# 468323_001_Interface.net
KiCad netlist of a schematic drawn in Altium Designer
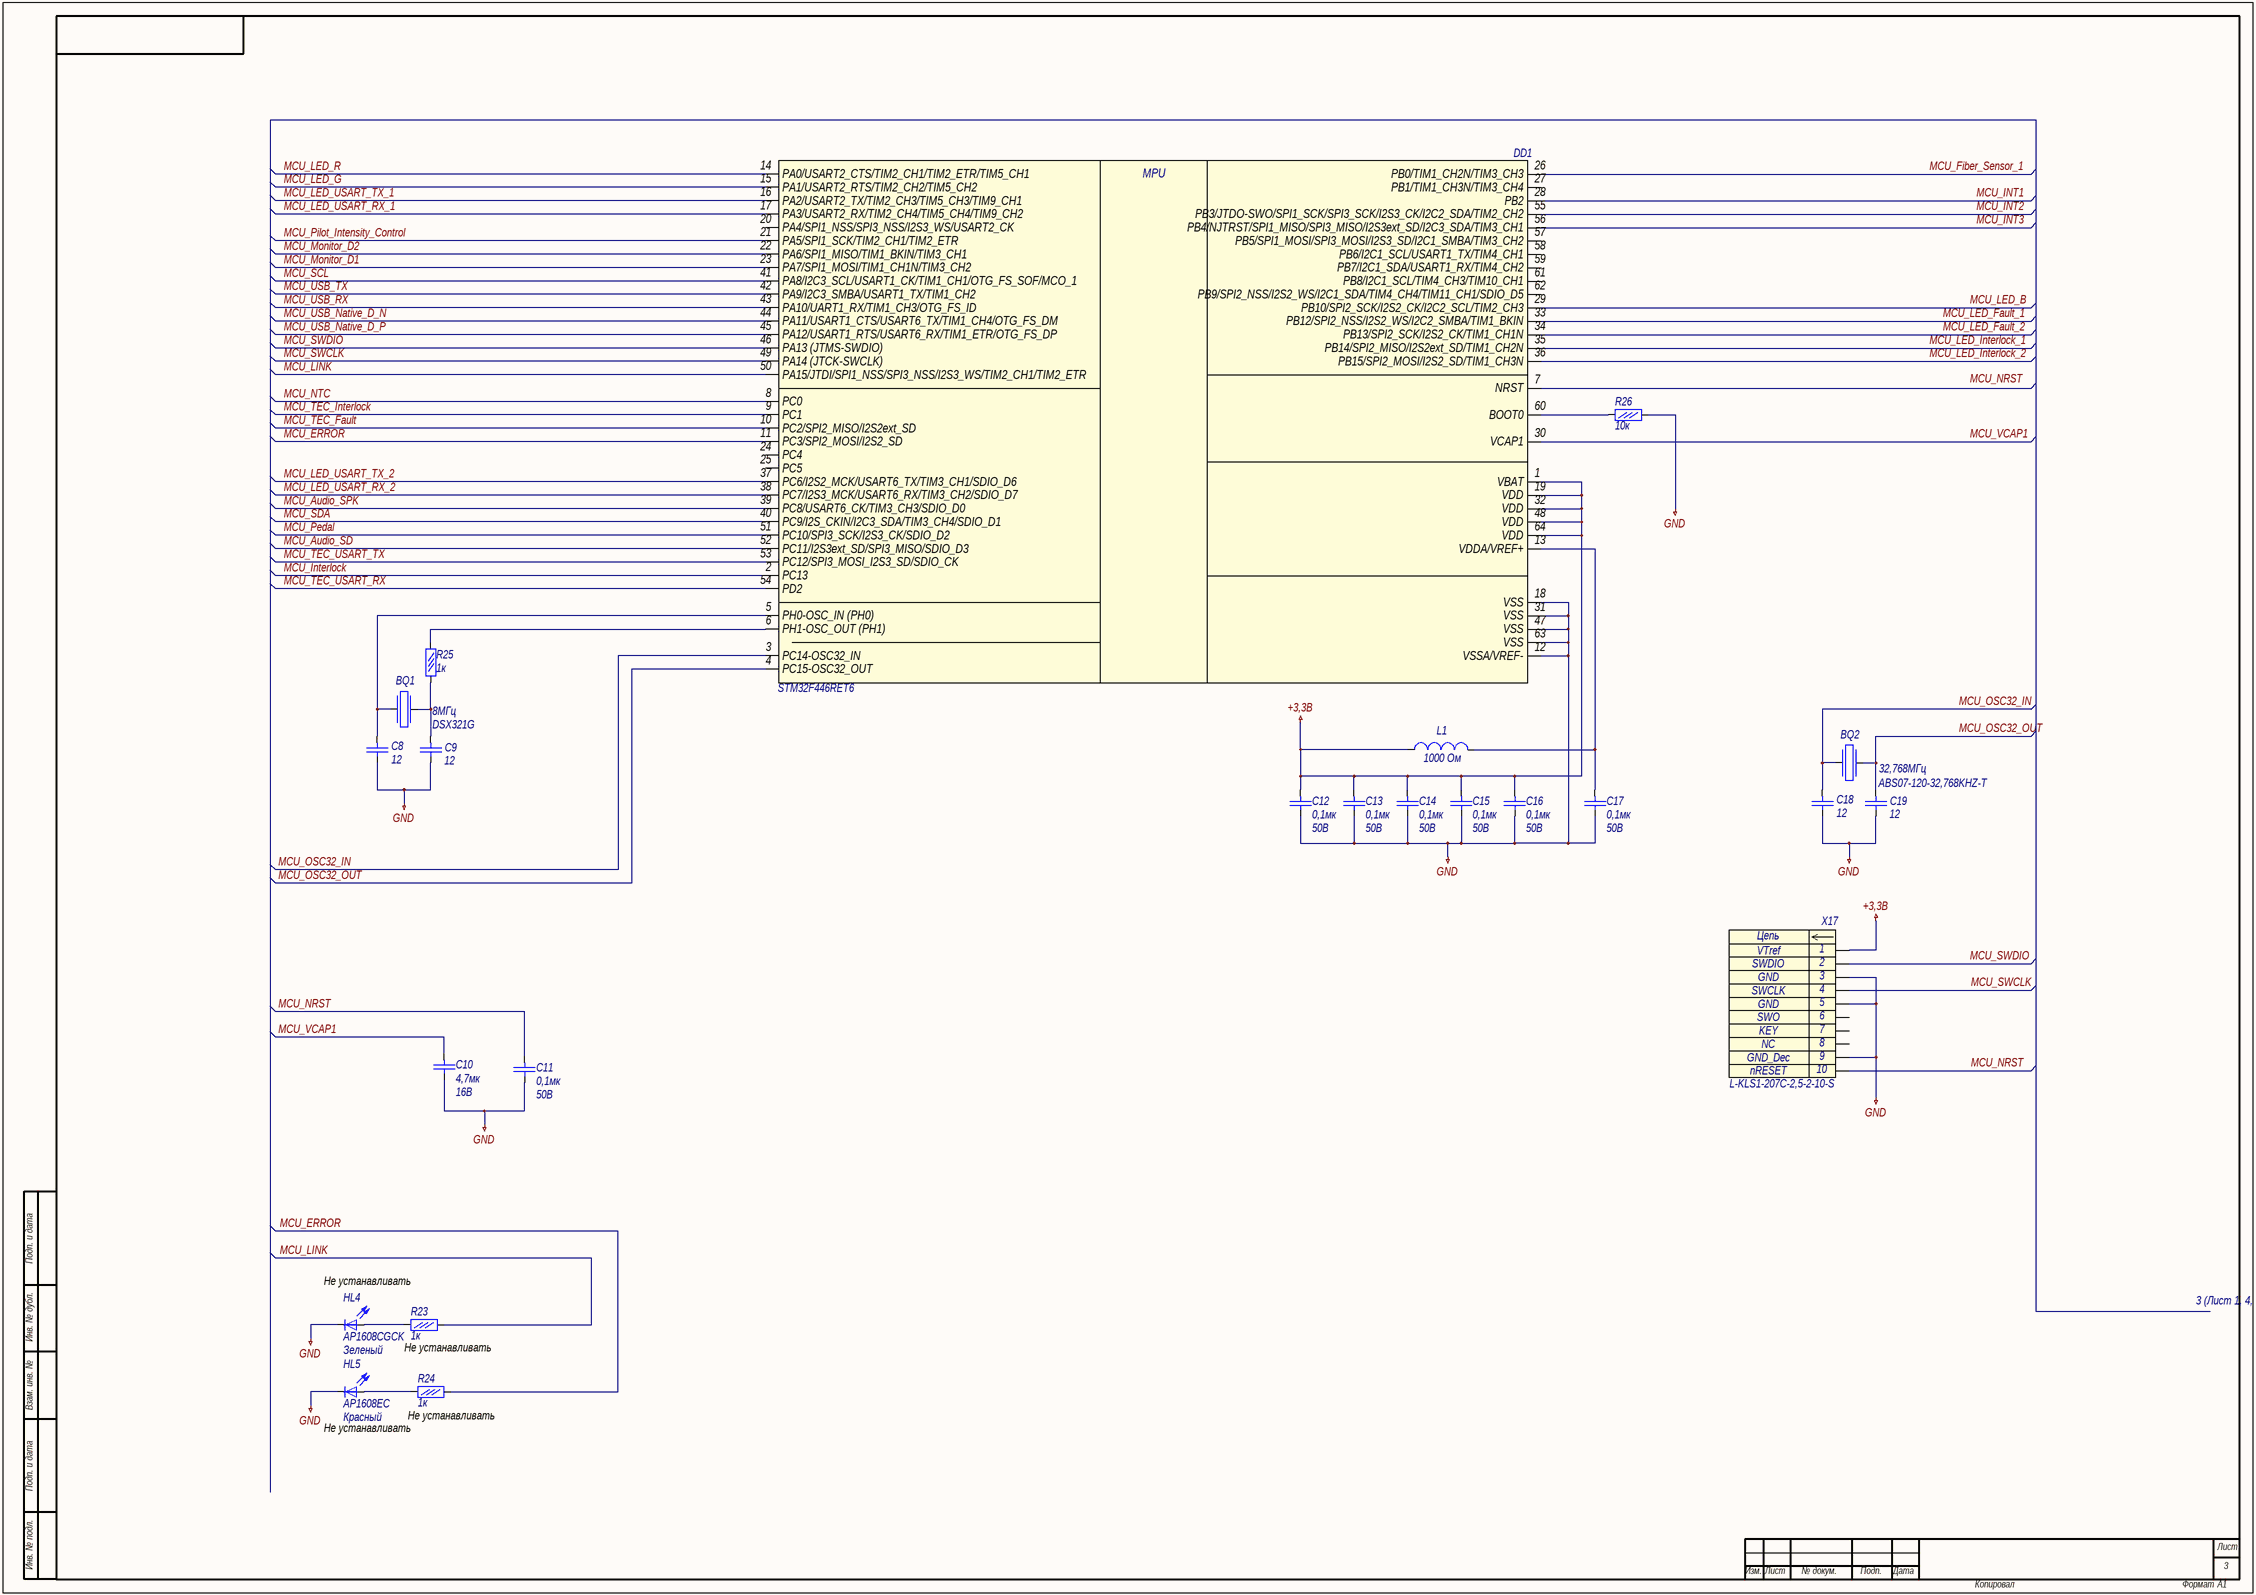
[diagram p0: РЕУН.468323.001_Interface.SchDoc]

(export (version "E")
  (design (tool "Eeschema 10.0.6"))
  (components
    (comp (ref "BQ1")
      (value "8МГц")
      (footprint "QSMD3.2x2.5_A")
      (description "Кварцевый резонатор")
      (fields (field (name "NAME") "DSX321G"))
      (libsource (lib "Library_Diana") (part "Crystal"))
    )
    (comp (ref "BQ2")
      (value "32,768МГц")
      (footprint "QSMD3.2x2.5_A")
      (description "Кварцевый резонатор")
      (fields (field (name "NAME") "ABS07-120-32,768KHZ-T"))
      (libsource (lib "") (part "Crystal_1"))
    )
    (comp (ref "C8")
      (value "12")
      (footprint "C0805_AA")
      (description "Конденсатор кер.")
      (libsource (lib "Library_Diana") (part "Конденсатор кер."))
    )
    (comp (ref "C9")
      (value "12")
      (footprint "C0805_AA")
      (description "Конденсатор кер.")
      (libsource (lib "Library_Diana") (part "Конденсатор кер."))
    )
    (comp (ref "C10")
      (value "4,7мк")
      (footprint "C0805_AA")
      (description "Конденсатор кер.")
      (fields (field (name "VOLTAGE") "16В"))
      (libsource (lib "Library_Diana") (part "Конденсатор кер."))
    )
    (comp (ref "C11")
      (value "0,1мк")
      (footprint "C0805_AA")
      (description "Конденсатор кер.")
      (fields (field (name "VOLTAGE") "50В"))
      (libsource (lib "Library_Diana") (part "Конденсатор кер."))
    )
    (comp (ref "C12")
      (value "0,1мк")
      (footprint "C0805_AA")
      (description "Конденсатор кер.")
      (fields (field (name "VOLTAGE") "50В"))
      (libsource (lib "Library_Diana") (part "Конденсатор кер."))
    )
    (comp (ref "C13")
      (value "0,1мк")
      (footprint "C0805_AA")
      (description "Конденсатор кер.")
      (fields (field (name "VOLTAGE") "50В"))
      (libsource (lib "Library_Diana") (part "Конденсатор кер."))
    )
    (comp (ref "C14")
      (value "0,1мк")
      (footprint "C0805_AA")
      (description "Конденсатор кер.")
      (fields (field (name "VOLTAGE") "50В"))
      (libsource (lib "Library_Diana") (part "Конденсатор кер."))
    )
    (comp (ref "C15")
      (value "0,1мк")
      (footprint "C0805_AA")
      (description "Конденсатор кер.")
      (fields (field (name "VOLTAGE") "50В"))
      (libsource (lib "Library_Diana") (part "Конденсатор кер."))
    )
    (comp (ref "C16")
      (value "0,1мк")
      (footprint "C0805_AA")
      (description "Конденсатор кер.")
      (fields (field (name "VOLTAGE") "50В"))
      (libsource (lib "Library_Diana") (part "Конденсатор кер."))
    )
    (comp (ref "C17")
      (value "0,1мк")
      (footprint "C0805_AA")
      (description "Конденсатор кер.")
      (fields (field (name "VOLTAGE") "50В"))
      (libsource (lib "Library_Diana") (part "Конденсатор кер."))
    )
    (comp (ref "C18")
      (value "12")
      (footprint "C0805_AA")
      (description "Конденсатор кер.")
      (libsource (lib "Library_Diana") (part "Конденсатор кер."))
    )
    (comp (ref "C19")
      (value "12")
      (footprint "C0805_AA")
      (description "Конденсатор кер.")
      (libsource (lib "Library_Diana") (part "Конденсатор кер."))
    )
    (comp (ref "DD1")
      (value "STM32F446RET6")
      (description "32-битный микроконтроллер")
      (libsource (lib "Library_Diana") (part "STM32F401RET6"))
    )
    (comp (ref "HL4")
      (value "AP1608CGCK")
      (description "Светодиод")
      (fields (field (name "NAME") "AP1608CGCK") (field (name "COLOR") "Зеленый"))
      (libsource (lib "Library_Diana") (part "led"))
    )
    (comp (ref "HL5")
      (value "AP1608EC")
      (description "Светодиод")
      (fields (field (name "NAME") "AP1608EC") (field (name "COLOR") "Красный"))
      (libsource (lib "Library_Diana") (part "led"))
    )
    (comp (ref "L1")
      (value "1000 Ом")
      (footprint "L0603_A")
      (description "Катушка индуктивности")
      (libsource (lib "Library_Diana") (part "Inductor"))
    )
    (comp (ref "R23")
      (value "1к")
      (footprint "R1206")
      (description "Резистор 0,05Вт")
      (libsource (lib "Library_Diana") (part "Резистор  0,05Вт"))
    )
    (comp (ref "R24")
      (value "1к")
      (footprint "R1206")
      (description "Резистор 0,05Вт")
      (libsource (lib "Library_Diana") (part "Резистор  0,05Вт"))
    )
    (comp (ref "R25")
      (value "1к")
      (footprint "R1206")
      (description "Резистор 0,05Вт")
      (libsource (lib "") (part "Резистор  0,05Вт_1"))
    )
    (comp (ref "R26")
      (value "10к")
      (footprint "R1206")
      (description "Резистор 0,05Вт")
      (libsource (lib "Library_Diana") (part "Резистор  0,05Вт"))
    )
    (comp (ref "X17")
      (value "L-KLS1-207C-2,5-2-10-S")
      (description "Разъем - 10 конт. вилка")
      (fields (field (name "NAME") "L-KLS1-207C-2,5-2-10-S"))
      (libsource (lib "Library_Diana") (part "x10-m"))
    )
  )
  (nets
    (net (code "1") (name "+3,3В") (class "Default")
      (node (ref "C12") (pin "2") (pinfunction "2_2") (pintype "passive"))
      (node (ref "C13") (pin "2") (pinfunction "2_2") (pintype "passive"))
      (node (ref "C14") (pin "2") (pinfunction "2_2") (pintype "passive"))
      (node (ref "C15") (pin "2") (pinfunction "2_2") (pintype "passive"))
      (node (ref "C16") (pin "2") (pinfunction "2_2") (pintype "passive"))
      (node (ref "DD1") (pin "1") (pinfunction "VBAT_1") (pintype "passive"))
      (node (ref "DD1") (pin "19") (pinfunction "VDD_19") (pintype "passive"))
      (node (ref "DD1") (pin "32") (pinfunction "VDD_32") (pintype "passive"))
      (node (ref "DD1") (pin "48") (pinfunction "VDD_48") (pintype "passive"))
      (node (ref "DD1") (pin "64") (pinfunction "VDD_64") (pintype "passive"))
      (node (ref "L1") (pin "1") (pinfunction "1_1") (pintype "passive"))
      (node (ref "X17") (pin "1") (pinfunction "1_1") (pintype "passive"))
    )
    (net (code "2") (name "/MCU_Audio_SD") (class "Default")
      (node (ref "DD1") (pin "52") (pinfunction "PC11/I2S3ext_SD/SPI3_MISO/SDIO_D3_52") (pintype "passive"))
    )
    (net (code "3") (name "/MCU_Audio_SPK") (class "Default")
      (node (ref "DD1") (pin "39") (pinfunction "PC8/USART6_CK/TIM3_CH3/SDIO_D0_39") (pintype "passive"))
    )
    (net (code "4") (name "/MCU_ERROR") (class "Default")
      (node (ref "DD1") (pin "11") (pinfunction "PC3/SPI2_MOSI/I2S2_SD_11") (pintype "passive"))
      (node (ref "R24") (pin "1") (pinfunction "1_1") (pintype "passive"))
    )
    (net (code "5") (name "/MCU_Fiber_Sensor_1") (class "Default")
      (node (ref "DD1") (pin "26") (pinfunction "PB0/TIM1_CH2N/TIM3_CH3_26") (pintype "passive"))
    )
    (net (code "6") (name "/MCU_INT1") (class "Default")
      (node (ref "DD1") (pin "28") (pinfunction "PB2_28") (pintype "passive"))
    )
    (net (code "7") (name "/MCU_INT2") (class "Default")
      (node (ref "DD1") (pin "55") (pinfunction "PB3/JTDO-SWO/SPI1_SCK/SPI3_SCK/I2S3_CK/I2C2_SDA/TIM2_CH2_55") (pintype "passive"))
    )
    (net (code "8") (name "/MCU_INT3") (class "Default")
      (node (ref "DD1") (pin "56") (pinfunction "PB4/NJTRST/SPI1_MISO/SPI3_MISO/I2S3ext_SD/I2C3_SDA/TIM3_CH1_56") (pintype "passive"))
    )
    (net (code "9") (name "/MCU_Interlock") (class "Default")
      (node (ref "DD1") (pin "2") (pinfunction "PC13_2") (pintype "passive"))
    )
    (net (code "10") (name "/MCU_LED_B") (class "Default")
      (node (ref "DD1") (pin "29") (pinfunction "PB10/SPI2_SCK/I2S2_CK/I2C2_SCL/TIM2_CH3_29") (pintype "passive"))
    )
    (net (code "11") (name "/MCU_LED_Fault_1") (class "Default")
      (node (ref "DD1") (pin "33") (pinfunction "PB12/SPI2_NSS/I2S2_WS/I2C2_SMBA/TIM1_BKIN_33") (pintype "passive"))
    )
    (net (code "12") (name "/MCU_LED_Fault_2") (class "Default")
      (node (ref "DD1") (pin "34") (pinfunction "PB13/SPI2_SCK/I2S2_CK/TIM1_CH1N_34") (pintype "passive"))
    )
    (net (code "13") (name "/MCU_LED_G") (class "Default")
      (node (ref "DD1") (pin "15") (pinfunction "PA1/USART2_RTS/TIM2_CH2/TIM5_CH2_15") (pintype "passive"))
    )
    (net (code "14") (name "/MCU_LED_Interlock_1") (class "Default")
      (node (ref "DD1") (pin "35") (pinfunction "PB14/SPI2_MISO/I2S2ext_SD/TIM1_CH2N_35") (pintype "passive"))
    )
    (net (code "15") (name "/MCU_LED_Interlock_2") (class "Default")
      (node (ref "DD1") (pin "36") (pinfunction "PB15/SPI2_MOSI/I2S2_SD/TIM1_CH3N_36") (pintype "passive"))
    )
    (net (code "16") (name "/MCU_LED_R") (class "Default")
      (node (ref "DD1") (pin "14") (pinfunction "PA0/USART2_CTS/TIM2_CH1/TIM2_ETR/TIM5_CH1_14") (pintype "passive"))
    )
    (net (code "17") (name "/MCU_LED_USART_RX_1") (class "Default")
      (node (ref "DD1") (pin "17") (pinfunction "PA3/USART2_RX/TIM2_CH4/TIM5_CH4/TIM9_CH2_17") (pintype "passive"))
    )
    (net (code "18") (name "/MCU_LED_USART_RX_2") (class "Default")
      (node (ref "DD1") (pin "38") (pinfunction "PC7/I2S3_MCK/USART6_RX/TIM3_CH2/SDIO_D7_38") (pintype "passive"))
    )
    (net (code "19") (name "/MCU_LED_USART_TX_1") (class "Default")
      (node (ref "DD1") (pin "16") (pinfunction "PA2/USART2_TX/TIM2_CH3/TIM5_CH3/TIM9_CH1_16") (pintype "passive"))
    )
    (net (code "20") (name "/MCU_LED_USART_TX_2") (class "Default")
      (node (ref "DD1") (pin "37") (pinfunction "PC6/I2S2_MCK/USART6_TX/TIM3_CH1/SDIO_D6_37") (pintype "passive"))
    )
    (net (code "21") (name "/MCU_LINK") (class "Default")
      (node (ref "DD1") (pin "50") (pinfunction "PA15/JTDI/SPI1_NSS/SPI3_NSS/I2S3_WS/TIM2_CH1/TIM2_ETR_50") (pintype "passive"))
      (node (ref "R23") (pin "1") (pinfunction "1_1") (pintype "passive"))
    )
    (net (code "22") (name "/MCU_Monitor_D1") (class "Default")
      (node (ref "DD1") (pin "23") (pinfunction "PA7/SPI1_MOSI/TIM1_CH1N/TIM3_CH2_23") (pintype "passive"))
    )
    (net (code "23") (name "/MCU_Monitor_D2") (class "Default")
      (node (ref "DD1") (pin "22") (pinfunction "PA6/SPI1_MISO/TIM1_BKIN/TIM3_CH1_22") (pintype "passive"))
    )
    (net (code "24") (name "/MCU_NRST") (class "Default")
      (node (ref "C11") (pin "2") (pinfunction "2_2") (pintype "passive"))
      (node (ref "X17") (pin "10") (pinfunction "10_10") (pintype "passive"))
    )
    (net (code "25") (name "/MCU_NTC") (class "Default")
      (node (ref "DD1") (pin "8") (pinfunction "PC0_8") (pintype "passive"))
    )
    (net (code "26") (name "/MCU_OSC32_IN") (class "Default")
      (node (ref "BQ2") (pin "2") (pinfunction "2_2") (pintype "passive"))
      (node (ref "C18") (pin "2") (pinfunction "2_2") (pintype "passive"))
      (node (ref "DD1") (pin "3") (pinfunction "PC14-OSC32_IN_3") (pintype "passive"))
    )
    (net (code "27") (name "/MCU_OSC32_OUT") (class "Default")
      (node (ref "BQ2") (pin "1") (pinfunction "1_1") (pintype "passive"))
      (node (ref "C19") (pin "2") (pinfunction "2_2") (pintype "passive"))
      (node (ref "DD1") (pin "4") (pinfunction "PC15-OSC32_OUT_4") (pintype "passive"))
    )
    (net (code "28") (name "/MCU_Pedal") (class "Default")
      (node (ref "DD1") (pin "51") (pinfunction "PC10/SPI3_SCK/I2S3_CK/SDIO_D2_51") (pintype "passive"))
    )
    (net (code "29") (name "/MCU_Pilot_Intensity_Control") (class "Default")
      (node (ref "DD1") (pin "21") (pinfunction "PA5/SPI1_SCK/TIM2_CH1/TIM2_ETR_21") (pintype "passive"))
    )
    (net (code "30") (name "/MCU_SCL") (class "Default")
      (node (ref "DD1") (pin "41") (pinfunction "PA8/I2C3_SCL/USART1_CK/TIM1_CH1/OTG_FS_SOF/MCO_1_41") (pintype "passive"))
    )
    (net (code "31") (name "/MCU_SDA") (class "Default")
      (node (ref "DD1") (pin "40") (pinfunction "PC9/I2S_CKIN/I2C3_SDA/TIM3_CH4/SDIO_D1_40") (pintype "passive"))
    )
    (net (code "32") (name "/MCU_SWCLK") (class "Default")
      (node (ref "DD1") (pin "49") (pinfunction "PA14_(JTCK-SWCLK)_49") (pintype "passive"))
      (node (ref "X17") (pin "4") (pinfunction "4_4") (pintype "passive"))
    )
    (net (code "33") (name "/MCU_SWDIO") (class "Default")
      (node (ref "DD1") (pin "46") (pinfunction "PA13_(JTMS-SWDIO)_46") (pintype "passive"))
      (node (ref "X17") (pin "2") (pinfunction "2_2") (pintype "passive"))
    )
    (net (code "34") (name "/MCU_TEC_Fault") (class "Default")
      (node (ref "DD1") (pin "10") (pinfunction "PC2/SPI2_MISO/I2S2ext_SD_10") (pintype "passive"))
    )
    (net (code "35") (name "/MCU_TEC_Interlock") (class "Default")
      (node (ref "DD1") (pin "9") (pinfunction "PC1_9") (pintype "passive"))
    )
    (net (code "36") (name "/MCU_TEC_USART_RX") (class "Default")
      (node (ref "DD1") (pin "54") (pinfunction "PD2_54") (pintype "passive"))
    )
    (net (code "37") (name "/MCU_TEC_USART_TX") (class "Default")
      (node (ref "DD1") (pin "53") (pinfunction "PC12/SPI3_MOSI_I2S3_SD/SDIO_CK_53") (pintype "passive"))
    )
    (net (code "38") (name "/MCU_USB_Native_D_N") (class "Default")
      (node (ref "DD1") (pin "44") (pinfunction "PA11/USART1_CTS/USART6_TX/TIM1_CH4/OTG_FS_DM_44") (pintype "passive"))
    )
    (net (code "39") (name "/MCU_USB_Native_D_P") (class "Default")
      (node (ref "DD1") (pin "45") (pinfunction "PA12/USART1_RTS/USART6_RX/TIM1_ETR/OTG_FS_DP_45") (pintype "passive"))
    )
    (net (code "40") (name "/MCU_USB_RX") (class "Default")
      (node (ref "DD1") (pin "43") (pinfunction "PA10/UART1_RX/TIM1_CH3/OTG_FS_ID_43") (pintype "passive"))
    )
    (net (code "41") (name "/MCU_USB_TX") (class "Default")
      (node (ref "DD1") (pin "42") (pinfunction "PA9/I2C3_SMBA/USART1_TX/TIM1_CH2_42") (pintype "passive"))
    )
    (net (code "42") (name "/MCU_VCAP1") (class "Default")
      (node (ref "C10") (pin "2") (pinfunction "2_2") (pintype "passive"))
      (node (ref "DD1") (pin "30") (pinfunction "VCAP1_30") (pintype "passive"))
    )
    (net (code "43") (name "GND") (class "Default")
      (node (ref "C10") (pin "1") (pinfunction "1_1") (pintype "passive"))
      (node (ref "C11") (pin "1") (pinfunction "1_1") (pintype "passive"))
      (node (ref "C12") (pin "1") (pinfunction "1_1") (pintype "passive"))
      (node (ref "C13") (pin "1") (pinfunction "1_1") (pintype "passive"))
      (node (ref "C14") (pin "1") (pinfunction "1_1") (pintype "passive"))
      (node (ref "C15") (pin "1") (pinfunction "1_1") (pintype "passive"))
      (node (ref "C16") (pin "1") (pinfunction "1_1") (pintype "passive"))
      (node (ref "C17") (pin "1") (pinfunction "1_1") (pintype "passive"))
      (node (ref "C18") (pin "1") (pinfunction "1_1") (pintype "passive"))
      (node (ref "C19") (pin "1") (pinfunction "1_1") (pintype "passive"))
      (node (ref "C8") (pin "1") (pinfunction "1_1") (pintype "passive"))
      (node (ref "C9") (pin "1") (pinfunction "1_1") (pintype "passive"))
      (node (ref "DD1") (pin "12") (pinfunction "VSSA/VREF-_12") (pintype "passive"))
      (node (ref "DD1") (pin "18") (pinfunction "VSS_18") (pintype "passive"))
      (node (ref "DD1") (pin "31") (pinfunction "VSS_31") (pintype "passive"))
      (node (ref "DD1") (pin "47") (pinfunction "VSS_47") (pintype "passive"))
      (node (ref "DD1") (pin "63") (pinfunction "VSS_63") (pintype "passive"))
      (node (ref "HL4") (pin "2") (pinfunction "K_2") (pintype "passive"))
      (node (ref "HL5") (pin "2") (pinfunction "K_2") (pintype "passive"))
      (node (ref "R26") (pin "1") (pinfunction "1_1") (pintype "passive"))
      (node (ref "X17") (pin "3") (pinfunction "3_3") (pintype "passive"))
      (node (ref "X17") (pin "5") (pinfunction "5_5") (pintype "passive"))
      (node (ref "X17") (pin "9") (pinfunction "9_9") (pintype "passive"))
    )
    (net (code "44") (name "Net-(BQ1-Pad2)") (class "Default")
      (node (ref "BQ1") (pin "2") (pinfunction "2_2") (pintype "passive"))
      (node (ref "C9") (pin "2") (pinfunction "2_2") (pintype "passive"))
      (node (ref "R25") (pin "1") (pinfunction "1_1") (pintype "passive"))
    )
    (net (code "45") (name "Net-(DD1-BOOT0)") (class "Default")
      (node (ref "DD1") (pin "60") (pinfunction "BOOT0_60") (pintype "passive"))
      (node (ref "R26") (pin "2") (pinfunction "2_2") (pintype "passive"))
    )
    (net (code "46") (name "Net-(DD1-PH0-OSC_IN_(PH0))") (class "Default")
      (node (ref "BQ1") (pin "1") (pinfunction "1_1") (pintype "passive"))
      (node (ref "C8") (pin "2") (pinfunction "2_2") (pintype "passive"))
      (node (ref "DD1") (pin "5") (pinfunction "PH0-OSC_IN_(PH0)_5") (pintype "passive"))
    )
    (net (code "47") (name "Net-(DD1-PH1-OSC_OUT_(PH1))") (class "Default")
      (node (ref "DD1") (pin "6") (pinfunction "PH1-OSC_OUT_(PH1)_6") (pintype "passive"))
      (node (ref "R25") (pin "2") (pinfunction "2_2") (pintype "passive"))
    )
    (net (code "48") (name "Net-(DD1-VDDA{slash}VREF+)") (class "Default")
      (node (ref "C17") (pin "2") (pinfunction "2_2") (pintype "passive"))
      (node (ref "DD1") (pin "13") (pinfunction "VDDA/VREF+_13") (pintype "passive"))
      (node (ref "L1") (pin "2") (pinfunction "2_2") (pintype "passive"))
    )
    (net (code "49") (name "Net-(HL4-A)") (class "Default")
      (node (ref "HL4") (pin "1") (pinfunction "A_1") (pintype "passive"))
      (node (ref "R23") (pin "2") (pinfunction "2_2") (pintype "passive"))
    )
    (net (code "50") (name "Net-(HL5-A)") (class "Default")
      (node (ref "HL5") (pin "1") (pinfunction "A_1") (pintype "passive"))
      (node (ref "R24") (pin "2") (pinfunction "2_2") (pintype "passive"))
    )
    (net (code "51") (name "unconnected-(DD1-NRST-Pad7)") (class "Default")
      (node (ref "DD1") (pin "7") (pinfunction "NRST_7") (pintype "passive"))
    )
    (net (code "52") (name "unconnected-(DD1-PA4{slash}SPI1_NSS{slash}SPI3_NSS{slash}I2S3_WS{slash}USART2_CK-Pad20)") (class "Default")
      (node (ref "DD1") (pin "20") (pinfunction "PA4/SPI1_NSS/SPI3_NSS/I2S3_WS/USART2_CK_20") (pintype "passive"))
    )
    (net (code "53") (name "unconnected-(DD1-PB1{slash}TIM1_CH3N{slash}TIM3_CH4-Pad27)") (class "Default")
      (node (ref "DD1") (pin "27") (pinfunction "PB1/TIM1_CH3N/TIM3_CH4_27") (pintype "passive"))
    )
    (net (code "54") (name "unconnected-(DD1-PB5{slash}SPI1_MOSI{slash}SPI3_MOSI{slash}I2S3_SD{slash}I2C1_SMBA{slash}TIM3_CH2-Pad57)") (class "Default")
      (node (ref "DD1") (pin "57") (pinfunction "PB5/SPI1_MOSI/SPI3_MOSI/I2S3_SD/I2C1_SMBA/TIM3_CH2_57") (pintype "passive"))
    )
    (net (code "55") (name "unconnected-(DD1-PB6{slash}I2C1_SCL{slash}USART1_TX{slash}TIM4_CH1-Pad58)") (class "Default")
      (node (ref "DD1") (pin "58") (pinfunction "PB6/I2C1_SCL/USART1_TX/TIM4_CH1_58") (pintype "passive"))
    )
    (net (code "56") (name "unconnected-(DD1-PB7{slash}I2C1_SDA{slash}USART1_RX{slash}TIM4_CH2-Pad59)") (class "Default")
      (node (ref "DD1") (pin "59") (pinfunction "PB7/I2C1_SDA/USART1_RX/TIM4_CH2_59") (pintype "passive"))
    )
    (net (code "57") (name "unconnected-(DD1-PB8{slash}I2C1_SCL{slash}TIM4_CH3{slash}TIM10_CH1-Pad61)") (class "Default")
      (node (ref "DD1") (pin "61") (pinfunction "PB8/I2C1_SCL/TIM4_CH3/TIM10_CH1_61") (pintype "passive"))
    )
    (net (code "58") (name "unconnected-(DD1-PB9{slash}SPI2_NSS{slash}I2S2_WS{slash}I2C1_SDA{slash}TIM4_CH4{slash}TIM11_CH1{slash}SDIO_D5-Pad62)") (class "Default")
      (node (ref "DD1") (pin "62") (pinfunction "PB9/SPI2_NSS/I2S2_WS/I2C1_SDA/TIM4_CH4/TIM11_CH1/SDIO_D5_62") (pintype "passive"))
    )
    (net (code "59") (name "unconnected-(DD1-PC4-Pad24)") (class "Default")
      (node (ref "DD1") (pin "24") (pinfunction "PC4_24") (pintype "passive"))
    )
    (net (code "60") (name "unconnected-(DD1-PC5-Pad25)") (class "Default")
      (node (ref "DD1") (pin "25") (pinfunction "PC5_25") (pintype "passive"))
    )
    (net (code "61") (name "unconnected-(X17-Pad6)") (class "Default")
      (node (ref "X17") (pin "6") (pinfunction "6_6") (pintype "passive"))
    )
    (net (code "62") (name "unconnected-(X17-Pad7)") (class "Default")
      (node (ref "X17") (pin "7") (pinfunction "7_7") (pintype "passive"))
    )
    (net (code "63") (name "unconnected-(X17-Pad8)") (class "Default")
      (node (ref "X17") (pin "8") (pinfunction "8_8") (pintype "passive"))
    )
  )
)
